# Temperature.net
KiCad netlist of a schematic drawn in EAGLE
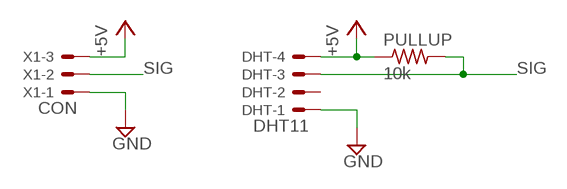
[diagram p0: schematic, sheet 1]

(export (version "E")
  (design (tool "Eeschema 10.0.6"))
  (components
    (comp (ref "DHT")
      (value "DHT11")
      (footprint "eagle-import:22-23-2041")
      (fields (field (name "MF") "MOLEX") (field (name "MPN") "22-23-2041"))
      (libsource (lib "eagle-import") (part "22-23-2041"))
    )
    (comp (ref "PULLUP")
      (value "10k")
      (footprint "eagle-import:0204_7")
      (libsource (lib "eagle-import") (part "R-US_0204/7"))
    )
    (comp (ref "X1")
      (value "CON")
      (footprint "eagle-import:22-23-2031")
      (fields (field (name "MF") "MOLEX") (field (name "MPN") "22-23-2031"))
      (libsource (lib "eagle-import") (part "22-23-2031"))
    )
  )
  (nets
    (net (code "1") (name "+5V") (class "Default")
      (node (ref "DHT") (pin "4") (pinfunction "S_4") (pintype "passive"))
      (node (ref "PULLUP") (pin "1") (pinfunction "1_1") (pintype "passive"))
      (node (ref "X1") (pin "3") (pinfunction "S_3") (pintype "passive"))
    )
    (net (code "2") (name "/SIG") (class "Default")
      (node (ref "DHT") (pin "3") (pinfunction "S_3") (pintype "passive"))
      (node (ref "PULLUP") (pin "2") (pinfunction "2_2") (pintype "passive"))
      (node (ref "X1") (pin "2") (pinfunction "S_2") (pintype "passive"))
    )
    (net (code "3") (name "GND") (class "Default")
      (node (ref "DHT") (pin "1") (pinfunction "S_1") (pintype "passive"))
      (node (ref "X1") (pin "1") (pinfunction "S_1") (pintype "passive"))
    )
    (net (code "4") (name "unconnected-(DHTB-S-Pad2)") (class "Default")
      (node (ref "DHT") (pin "2") (pinfunction "S_2") (pintype "passive"))
    )
  )
)
